# untitled.net
KiCad netlist of a schematic drawn in EAGLE
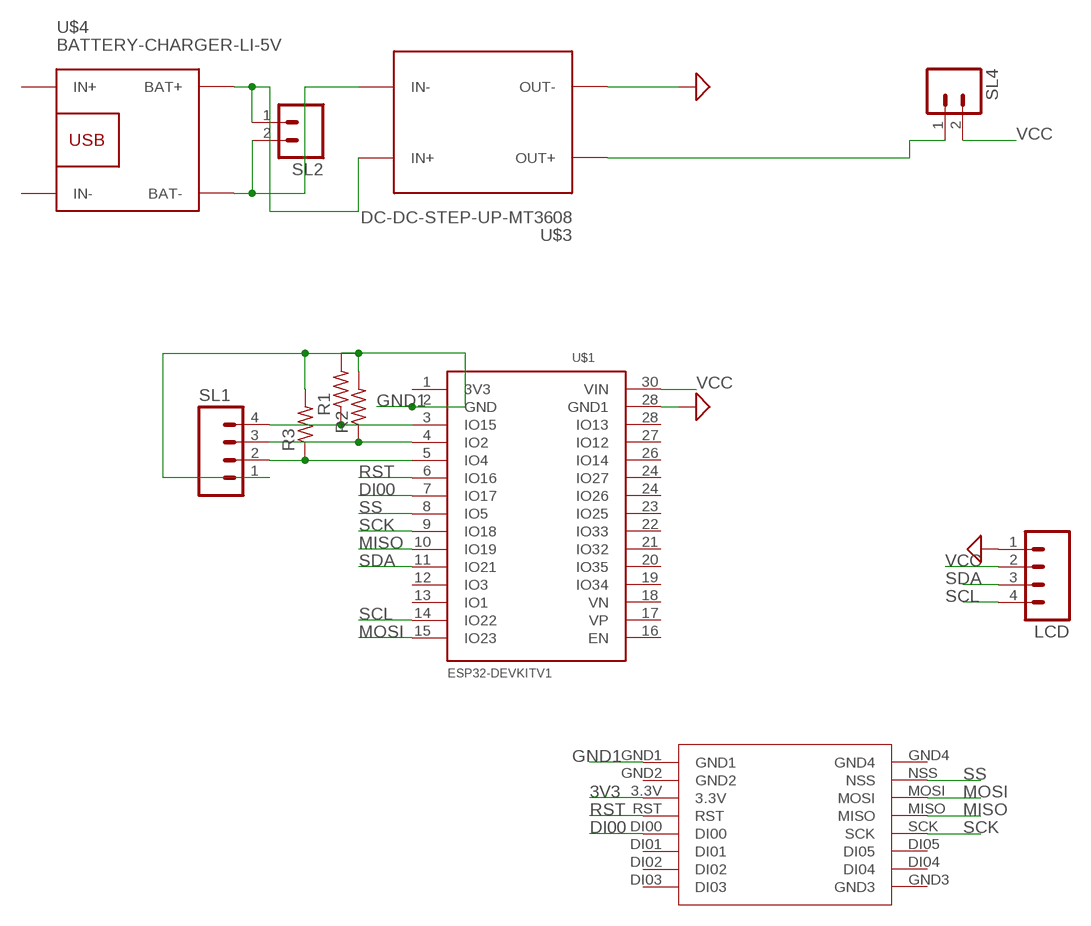
[diagram p0: schematic, sheet 1]

(export (version "E")
  (design (tool "Eeschema 10.0.6"))
  (components
    (comp (ref "LCD")
      (value "M04")
      (footprint "eagle-import:04P")
      (libsource (lib "eagle-import") (part "M04"))
    )
    (comp (ref "R1")
      (value "R-US_0207/10")
      (footprint "eagle-import:0207_10")
      (libsource (lib "eagle-import") (part "R-US_0207/10"))
    )
    (comp (ref "R2")
      (value "R-US_0207/10")
      (footprint "eagle-import:0207_10")
      (libsource (lib "eagle-import") (part "R-US_0207/10"))
    )
    (comp (ref "R3")
      (value "R-US_0207/10")
      (footprint "eagle-import:0207_10")
      (libsource (lib "eagle-import") (part "R-US_0207/10"))
    )
    (comp (ref "SL1")
      (value "M04")
      (footprint "eagle-import:04P")
      (libsource (lib "eagle-import") (part "M04"))
    )
    (comp (ref "SL2")
      (value "M02")
      (footprint "eagle-import:02P")
      (libsource (lib "eagle-import") (part "M02"))
    )
    (comp (ref "SL4")
      (value "M02")
      (footprint "eagle-import:02P")
      (libsource (lib "eagle-import") (part "M02"))
    )
    (comp (ref "U$1")
      (value "ESP32DEVKITV1")
      (footprint "eagle-import:ESP32-DEVKITV1")
      (libsource (lib "eagle-import") (part "ESP32DEVKITV1"))
    )
    (comp (ref "U$2")
      (value "LORASX1278")
      (footprint "eagle-import:LORASX1278")
      (libsource (lib "eagle-import") (part "LORASX1278"))
    )
    (comp (ref "U$3")
      (value "DC-DC-STEP-UP-MT3608")
      (footprint "eagle-import:DC-DC-STEP-UP-MT3608")
      (libsource (lib "eagle-import") (part "DC-DC-STEP-UP-MT3608"))
    )
    (comp (ref "U$4")
      (value "BATTERY-CHARGER-LI-5V")
      (footprint "eagle-import:BATTERY-CHARGER-LI-5V")
      (libsource (lib "eagle-import") (part "BATTERY-CHARGER-LI-5V"))
    )
  )
  (nets
    (net (code "1") (name "/3V3") (class "Default")
      (node (ref "U$2") (pin "3.3V") (pinfunction "3.3V_3.3V") (pintype "bidirectional"))
    )
    (net (code "2") (name "/DI00") (class "Default")
      (node (ref "U$1") (pin "7") (pinfunction "IO17_7") (pintype "bidirectional"))
      (node (ref "U$2") (pin "DI00") (pinfunction "DI00_DI00") (pintype "bidirectional"))
    )
    (net (code "3") (name "/GND1") (class "Default")
      (node (ref "R1") (pin "2") (pinfunction "2_2") (pintype "passive"))
      (node (ref "R2") (pin "2") (pinfunction "2_2") (pintype "passive"))
      (node (ref "R3") (pin "2") (pinfunction "2_2") (pintype "passive"))
      (node (ref "SL1") (pin "1") (pinfunction "1_1") (pintype "passive"))
      (node (ref "U$1") (pin "2") (pinfunction "GND_2") (pintype "bidirectional"))
      (node (ref "U$2") (pin "GND1") (pinfunction "GND1_GND1") (pintype "bidirectional"))
    )
    (net (code "4") (name "/MISO") (class "Default")
      (node (ref "U$1") (pin "10") (pinfunction "IO19_10") (pintype "bidirectional"))
      (node (ref "U$2") (pin "MISO") (pinfunction "MISO_MISO") (pintype "bidirectional"))
    )
    (net (code "5") (name "/MOSI") (class "Default")
      (node (ref "U$1") (pin "15") (pinfunction "IO23_15") (pintype "bidirectional"))
      (node (ref "U$2") (pin "MOSI") (pinfunction "MOSI_MOSI") (pintype "bidirectional"))
    )
    (net (code "6") (name "/RST") (class "Default")
      (node (ref "U$1") (pin "6") (pinfunction "IO16_6") (pintype "bidirectional"))
      (node (ref "U$2") (pin "RST") (pinfunction "RST_RST") (pintype "bidirectional"))
    )
    (net (code "7") (name "/SCK") (class "Default")
      (node (ref "U$1") (pin "9") (pinfunction "IO18_9") (pintype "bidirectional"))
      (node (ref "U$2") (pin "SCK") (pinfunction "SCK_SCK") (pintype "bidirectional"))
    )
    (net (code "8") (name "/SCL") (class "Default")
      (node (ref "LCD") (pin "4") (pinfunction "4_4") (pintype "passive"))
      (node (ref "U$1") (pin "14") (pinfunction "IO22_14") (pintype "bidirectional"))
    )
    (net (code "9") (name "/SDA") (class "Default")
      (node (ref "LCD") (pin "3") (pinfunction "3_3") (pintype "passive"))
      (node (ref "U$1") (pin "11") (pinfunction "IO21_11") (pintype "bidirectional"))
    )
    (net (code "10") (name "/SS") (class "Default")
      (node (ref "U$1") (pin "8") (pinfunction "IO5_8") (pintype "bidirectional"))
      (node (ref "U$2") (pin "NSS") (pinfunction "NSS_NSS") (pintype "bidirectional"))
    )
    (net (code "11") (name "/VCC") (class "Default")
      (node (ref "LCD") (pin "2") (pinfunction "2_2") (pintype "passive"))
      (node (ref "SL4") (pin "2") (pinfunction "2_2") (pintype "passive"))
      (node (ref "U$1") (pin "30") (pinfunction "VIN_30") (pintype "bidirectional"))
    )
    (net (code "12") (name "Net-(SL2-Pad1)") (class "Default")
      (node (ref "SL2") (pin "1") (pinfunction "1_1") (pintype "passive"))
      (node (ref "U$3") (pin "IN+") (pinfunction "IN+_IN+") (pintype "bidirectional"))
      (node (ref "U$4") (pin "BAT+") (pinfunction "BAT+_BAT+") (pintype "bidirectional"))
    )
    (net (code "13") (name "Net-(SL2-Pad2)") (class "Default")
      (node (ref "SL2") (pin "2") (pinfunction "2_2") (pintype "passive"))
      (node (ref "U$3") (pin "IN-") (pinfunction "IN-_IN-") (pintype "bidirectional"))
      (node (ref "U$4") (pin "BAT-") (pinfunction "BAT-_BAT-") (pintype "bidirectional"))
    )
    (net (code "14") (name "Net-(SL4-Pad1)") (class "Default")
      (node (ref "SL4") (pin "1") (pinfunction "1_1") (pintype "passive"))
      (node (ref "U$3") (pin "OUT+") (pinfunction "OUT+_OUT+") (pintype "bidirectional"))
    )
    (net (code "15") (name "Net-(U$1-IO2)") (class "Default")
      (node (ref "R2") (pin "1") (pinfunction "1_1") (pintype "passive"))
      (node (ref "SL1") (pin "3") (pinfunction "3_3") (pintype "passive"))
      (node (ref "U$1") (pin "4") (pinfunction "IO2_4") (pintype "bidirectional"))
    )
    (net (code "16") (name "Net-(U$1-IO4)") (class "Default")
      (node (ref "R3") (pin "1") (pinfunction "1_1") (pintype "passive"))
      (node (ref "SL1") (pin "2") (pinfunction "2_2") (pintype "passive"))
      (node (ref "U$1") (pin "5") (pinfunction "IO4_5") (pintype "bidirectional"))
    )
    (net (code "17") (name "Net-(U$1-IO15)") (class "Default")
      (node (ref "R1") (pin "1") (pinfunction "1_1") (pintype "passive"))
      (node (ref "SL1") (pin "4") (pinfunction "4_4") (pintype "passive"))
      (node (ref "U$1") (pin "3") (pinfunction "IO15_3") (pintype "bidirectional"))
    )
    (net (code "18") (name "SUP") (class "Default")
      (node (ref "LCD") (pin "1") (pinfunction "1_1") (pintype "passive"))
      (node (ref "U$1") (pin "28") (pinfunction "GND1_28") (pintype "bidirectional"))
      (node (ref "U$3") (pin "OUT-") (pinfunction "OUT-_OUT-") (pintype "bidirectional"))
    )
    (net (code "19") (name "unconnected-(U$1-3V3-Pad1)") (class "Default")
      (node (ref "U$1") (pin "1") (pinfunction "3V3_1") (pintype "bidirectional"))
    )
    (net (code "20") (name "unconnected-(U$1-EN-Pad16)") (class "Default")
      (node (ref "U$1") (pin "16") (pinfunction "EN_16") (pintype "bidirectional"))
    )
    (net (code "21") (name "unconnected-(U$1-IO1-Pad13)") (class "Default")
      (node (ref "U$1") (pin "13") (pinfunction "IO1_13") (pintype "bidirectional"))
    )
    (net (code "22") (name "unconnected-(U$1-IO3-Pad12)") (class "Default")
      (node (ref "U$1") (pin "12") (pinfunction "IO3_12") (pintype "bidirectional"))
    )
    (net (code "23") (name "unconnected-(U$1-IO12-Pad27)") (class "Default")
      (node (ref "U$1") (pin "27") (pinfunction "IO12_27") (pintype "bidirectional"))
    )
    (net (code "24") (name "unconnected-(U$1-IO13-Pad28)") (class "Default")
      (node (ref "U$1") (pin "28") (pinfunction "IO13_28") (pintype "bidirectional"))
    )
    (net (code "25") (name "unconnected-(U$1-IO14-Pad26)") (class "Default")
      (node (ref "U$1") (pin "26") (pinfunction "IO14_26") (pintype "bidirectional"))
    )
    (net (code "26") (name "unconnected-(U$1-IO25-Pad23)") (class "Default")
      (node (ref "U$1") (pin "23") (pinfunction "IO25_23") (pintype "bidirectional"))
    )
    (net (code "27") (name "unconnected-(U$1-IO26-Pad24)") (class "Default")
      (node (ref "U$1") (pin "24") (pinfunction "IO26_24") (pintype "bidirectional"))
    )
    (net (code "28") (name "unconnected-(U$1-IO27-Pad24)") (class "Default")
      (node (ref "U$1") (pin "24") (pinfunction "IO27_24") (pintype "bidirectional"))
    )
    (net (code "29") (name "unconnected-(U$1-IO32-Pad21)") (class "Default")
      (node (ref "U$1") (pin "21") (pinfunction "IO32_21") (pintype "bidirectional"))
    )
    (net (code "30") (name "unconnected-(U$1-IO33-Pad22)") (class "Default")
      (node (ref "U$1") (pin "22") (pinfunction "IO33_22") (pintype "bidirectional"))
    )
    (net (code "31") (name "unconnected-(U$1-IO34-Pad19)") (class "Default")
      (node (ref "U$1") (pin "19") (pinfunction "IO34_19") (pintype "bidirectional"))
    )
    (net (code "32") (name "unconnected-(U$1-IO35-Pad20)") (class "Default")
      (node (ref "U$1") (pin "20") (pinfunction "IO35_20") (pintype "bidirectional"))
    )
    (net (code "33") (name "unconnected-(U$1-VN-Pad18)") (class "Default")
      (node (ref "U$1") (pin "18") (pinfunction "VN_18") (pintype "bidirectional"))
    )
    (net (code "34") (name "unconnected-(U$1-VP-Pad17)") (class "Default")
      (node (ref "U$1") (pin "17") (pinfunction "VP_17") (pintype "bidirectional"))
    )
    (net (code "35") (name "unconnected-(U$2-PadDI01)") (class "Default")
      (node (ref "U$2") (pin "DI01") (pinfunction "DI01_DI01") (pintype "bidirectional"))
    )
    (net (code "36") (name "unconnected-(U$2-PadDI02)") (class "Default")
      (node (ref "U$2") (pin "DI02") (pinfunction "DI02_DI02") (pintype "bidirectional"))
    )
    (net (code "37") (name "unconnected-(U$2-PadDI03)") (class "Default")
      (node (ref "U$2") (pin "DI03") (pinfunction "DI03_DI03") (pintype "bidirectional"))
    )
    (net (code "38") (name "unconnected-(U$2-PadDI04)") (class "Default")
      (node (ref "U$2") (pin "DI04") (pinfunction "DI04_DI04") (pintype "bidirectional"))
    )
    (net (code "39") (name "unconnected-(U$2-PadDI05)") (class "Default")
      (node (ref "U$2") (pin "DI05") (pinfunction "DI05_DI05") (pintype "bidirectional"))
    )
    (net (code "40") (name "unconnected-(U$2-PadGND2)") (class "Default")
      (node (ref "U$2") (pin "GND2") (pinfunction "GND2_GND2") (pintype "bidirectional"))
    )
    (net (code "41") (name "unconnected-(U$2-PadGND3)") (class "Default")
      (node (ref "U$2") (pin "GND3") (pinfunction "GND3_GND3") (pintype "bidirectional"))
    )
    (net (code "42") (name "unconnected-(U$2-PadGND4)") (class "Default")
      (node (ref "U$2") (pin "GND4") (pinfunction "GND4_GND4") (pintype "bidirectional"))
    )
    (net (code "43") (name "unconnected-(U$4-PadIN+)") (class "Default")
      (node (ref "U$4") (pin "IN+") (pinfunction "IN+_IN+") (pintype "bidirectional"))
    )
    (net (code "44") (name "unconnected-(U$4-PadIN-)") (class "Default")
      (node (ref "U$4") (pin "IN-") (pinfunction "IN-_IN-") (pintype "bidirectional"))
    )
  )
)
